# ButtonsBuzzerLeds.net
KiCad netlist of a schematic drawn in Altium Designer
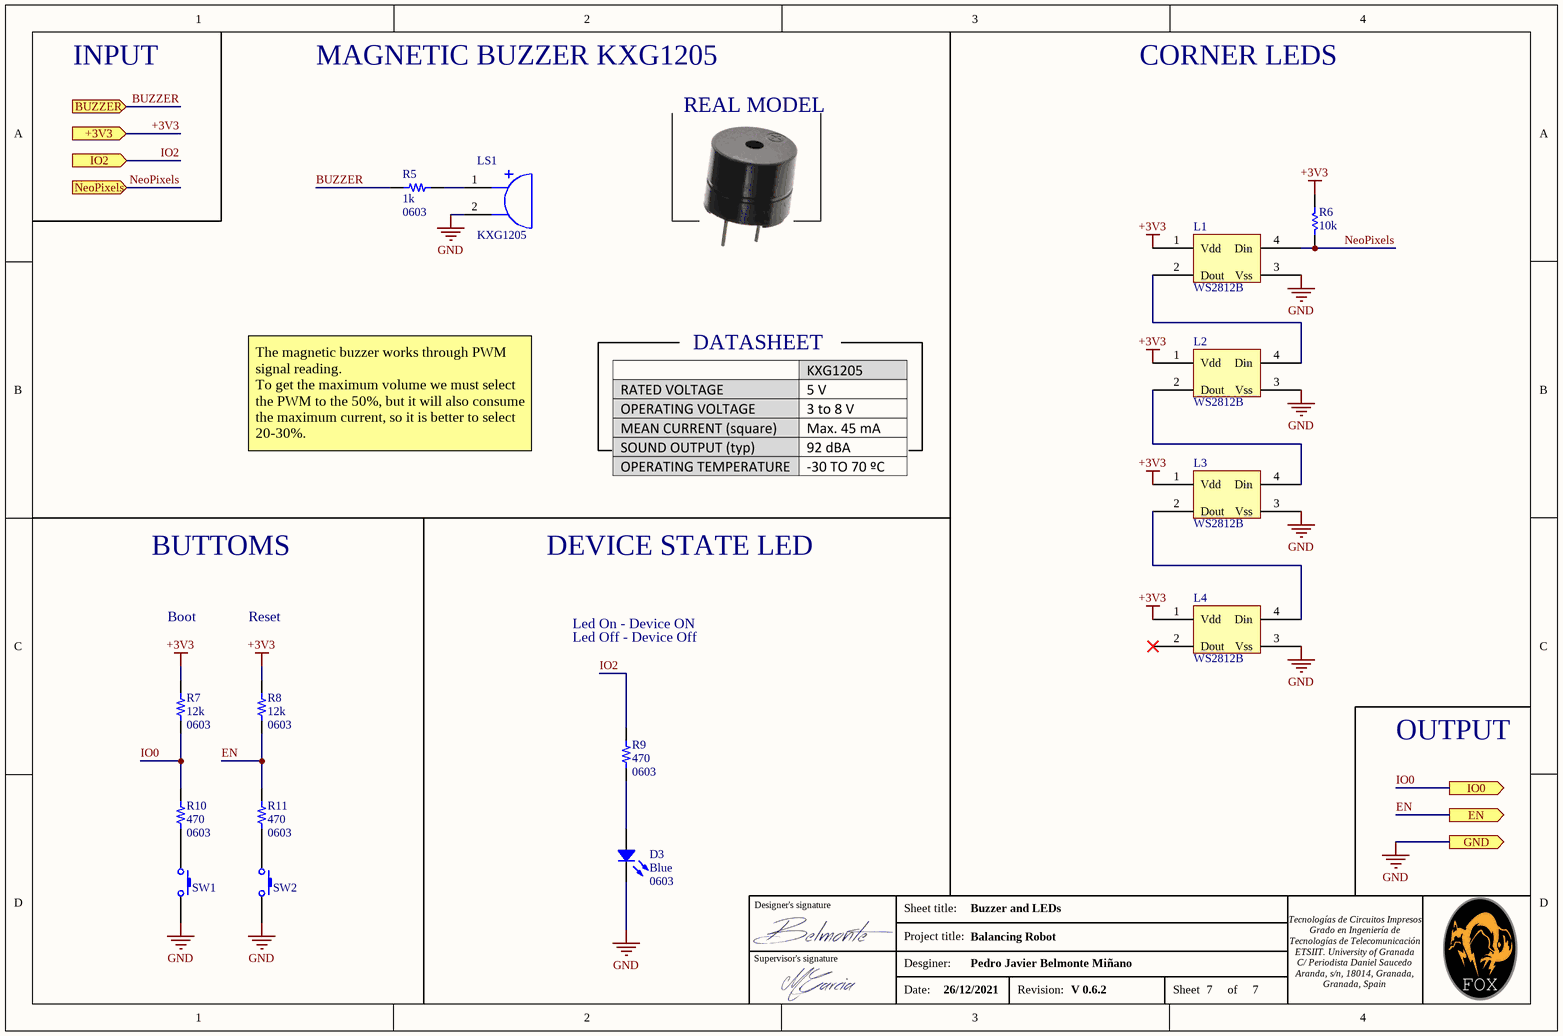
[diagram p0: ButtonsBuzzerLeds.SchDoc]

(export (version "E")
  (design (tool "Eeschema 10.0.6"))
  (components
    (comp (ref "D3")
      (value "Blue")
      (footprint "LED 0603_1608 BLUE")
      (description "LED BLUE 0603 SMD")
      (fields
        (field (name "PART NUMBER") "VLMB1300-GS08")
        (field (name "MANUFACTURER") "Vishay Semiconductor Opto Division")
        (field (name "SIZE") "0603")
      )
      (libsource (lib "ControlBoard") (part "LED"))
    )
    (comp (ref "L1")
      (value "WS2812B")
      (footprint "WS2812B")
      (libsource (lib "HeimdalLimiter") (part "WS2812B"))
    )
    (comp (ref "L2")
      (value "WS2812B")
      (footprint "WS2812B")
      (libsource (lib "HeimdalLimiter") (part "WS2812B"))
    )
    (comp (ref "L3")
      (value "WS2812B")
      (footprint "WS2812B")
      (libsource (lib "HeimdalLimiter") (part "WS2812B"))
    )
    (comp (ref "L4")
      (value "WS2812B")
      (footprint "WS2812B")
      (libsource (lib "HeimdalLimiter") (part "WS2812B"))
    )
    (comp (ref "LS1") (value "KXG1205") (footprint "BUZZER") (libsource (lib "ControlBoard") (part "Buzzer")))
    (comp (ref "R5")
      (value "1k")
      (footprint "RES 0603_1608")
      (description "RES SMD 1K OHM 1% 1/4W 0603")
      (fields
        (field (name "PART NUMBER") "CRCW06031K00FKEAHP")
        (field (name "MANUFACTURER") "Vishay Dale")
        (field (name "SIZE") "0603")
      )
      (libsource (lib "ControlBoard") (part "CRCW06031K00FKEAHP"))
    )
    (comp (ref "R6")
      (value "10k")
      (footprint "0805")
      (description "Resistor")
      (libsource (lib "HeimdalLimiter") (part "Resistor"))
    )
    (comp (ref "R7")
      (value "12k")
      (footprint "RES 0603_1608")
      (description "RES 12K OHM 5% 1/10W 0603")
      (fields
        (field (name "PART NUMBER") "RMCF0603JT12K0")
        (field (name "MANUFACTURER") "Stackpole Electronics Inc")
        (field (name "SIZE") "0603")
      )
      (libsource (lib "ControlBoard") (part "RMCF0603JT12K0"))
    )
    (comp (ref "R8")
      (value "12k")
      (footprint "RES 0603_1608")
      (description "RES 12K OHM 5% 1/10W 0603")
      (fields
        (field (name "PART NUMBER") "RMCF0603JT12K0")
        (field (name "MANUFACTURER") "Stackpole Electronics Inc")
        (field (name "SIZE") "0603")
      )
      (libsource (lib "ControlBoard") (part "RMCF0603JT12K0"))
    )
    (comp (ref "R9")
      (value "470")
      (footprint "RES 0603_1608")
      (description "RES 470 OHM 5% 1/10W 0603")
      (fields
        (field (name "PART NUMBER") "RMCF0603JT470R")
        (field (name "MANUFACTURER") "Stackpole Electronics Inc")
        (field (name "SIZE") "0603")
      )
      (libsource (lib "ControlBoard") (part "RMCF0603JT470R"))
    )
    (comp (ref "R10")
      (value "470")
      (footprint "RES 0603_1608")
      (description "RES 470 OHM 5% 1/10W 0603")
      (fields
        (field (name "PART NUMBER") "RMCF0603JT470R")
        (field (name "MANUFACTURER") "Stackpole Electronics Inc")
        (field (name "SIZE") "0603")
      )
      (libsource (lib "ControlBoard") (part "RMCF0603JT470R"))
    )
    (comp (ref "R11")
      (value "470")
      (footprint "RES 0603_1608")
      (description "RES 470 OHM 5% 1/10W 0603")
      (fields
        (field (name "PART NUMBER") "RMCF0603JT470R")
        (field (name "MANUFACTURER") "Stackpole Electronics Inc")
        (field (name "SIZE") "0603")
      )
      (libsource (lib "ControlBoard") (part "RMCF0603JT470R"))
    )
    (comp (ref "SW1")
      (value "FSMSMTR")
      (footprint "TECO-FSMSMTR_V")
      (description "FSMSM Push Button Switch, 50 mA, -35 to 85 degC, 2-Pin SMD, RoHS, Tape and Reel")
      (fields (field (name "MANUFACTURER") "TE Connectivity"))
      (libsource (lib "TopBoardLib") (part "CMP-2000-07501-1"))
    )
    (comp (ref "SW2")
      (value "FSMSMTR")
      (footprint "TECO-FSMSMTR_V")
      (description "FSMSM Push Button Switch, 50 mA, -35 to 85 degC, 2-Pin SMD, RoHS, Tape and Reel")
      (fields (field (name "MANUFACTURER") "TE Connectivity"))
      (libsource (lib "TopBoardLib") (part "CMP-2000-07501-1"))
    )
  )
  (nets
    (net (code "1") (name "+3V3") (class "Default")
      (node (ref "L1") (pin "1") (pinfunction "Vdd_1") (pintype "passive"))
      (node (ref "L2") (pin "1") (pinfunction "Vdd_1") (pintype "passive"))
      (node (ref "L3") (pin "1") (pinfunction "Vdd_1") (pintype "passive"))
      (node (ref "L4") (pin "1") (pinfunction "Vdd_1") (pintype "passive"))
      (node (ref "R6") (pin "1") (pinfunction "1_1") (pintype "passive"))
      (node (ref "R7") (pin "1") (pinfunction "1_1") (pintype "passive"))
      (node (ref "R8") (pin "1") (pinfunction "1_1") (pintype "passive"))
    )
    (net (code "2") (name "/BUZZER") (class "Default")
      (node (ref "R5") (pin "2") (pinfunction "2_2") (pintype "passive"))
    )
    (net (code "3") (name "/EN") (class "Default")
      (node (ref "R11") (pin "1") (pinfunction "1_1") (pintype "passive"))
      (node (ref "R8") (pin "2") (pinfunction "2_2") (pintype "passive"))
    )
    (net (code "4") (name "/IO0") (class "Default")
      (node (ref "R10") (pin "1") (pinfunction "1_1") (pintype "passive"))
      (node (ref "R7") (pin "2") (pinfunction "2_2") (pintype "passive"))
    )
    (net (code "5") (name "/IO2") (class "Default")
      (node (ref "R9") (pin "1") (pinfunction "1_1") (pintype "passive"))
    )
    (net (code "6") (name "/NeoPixels") (class "Default")
      (node (ref "L1") (pin "4") (pinfunction "Din_4") (pintype "passive"))
      (node (ref "R6") (pin "2") (pinfunction "2_2") (pintype "passive"))
    )
    (net (code "7") (name "GND") (class "Default")
      (node (ref "D3") (pin "2") (pinfunction "2_2") (pintype "passive"))
      (node (ref "L1") (pin "3") (pinfunction "Vss_3") (pintype "passive"))
      (node (ref "L2") (pin "3") (pinfunction "Vss_3") (pintype "passive"))
      (node (ref "L3") (pin "3") (pinfunction "Vss_3") (pintype "passive"))
      (node (ref "L4") (pin "3") (pinfunction "Vss_3") (pintype "passive"))
      (node (ref "LS1") (pin "2") (pinfunction "-_2") (pintype "passive"))
      (node (ref "SW1") (pin "2") (pinfunction "2_2") (pintype "passive"))
      (node (ref "SW2") (pin "2") (pinfunction "2_2") (pintype "passive"))
    )
    (net (code "8") (name "Net-(D3-Pad1)") (class "Default")
      (node (ref "D3") (pin "1") (pinfunction "1_1") (pintype "passive"))
      (node (ref "R9") (pin "2") (pinfunction "2_2") (pintype "passive"))
    )
    (net (code "9") (name "Net-(L1-Dout)") (class "Default")
      (node (ref "L1") (pin "2") (pinfunction "Dout_2") (pintype "passive"))
      (node (ref "L2") (pin "4") (pinfunction "Din_4") (pintype "passive"))
    )
    (net (code "10") (name "Net-(L2-Dout)") (class "Default")
      (node (ref "L2") (pin "2") (pinfunction "Dout_2") (pintype "passive"))
      (node (ref "L3") (pin "4") (pinfunction "Din_4") (pintype "passive"))
    )
    (net (code "11") (name "Net-(L3-Dout)") (class "Default")
      (node (ref "L3") (pin "2") (pinfunction "Dout_2") (pintype "passive"))
      (node (ref "L4") (pin "4") (pinfunction "Din_4") (pintype "passive"))
    )
    (net (code "12") (name "Net-(LS1-+)") (class "Default")
      (node (ref "LS1") (pin "1") (pinfunction "+_1") (pintype "passive"))
      (node (ref "R5") (pin "1") (pinfunction "1_1") (pintype "passive"))
    )
    (net (code "13") (name "Net-(R10-Pad2)") (class "Default")
      (node (ref "R10") (pin "2") (pinfunction "2_2") (pintype "passive"))
      (node (ref "SW1") (pin "1") (pinfunction "1_1") (pintype "passive"))
    )
    (net (code "14") (name "Net-(R11-Pad2)") (class "Default")
      (node (ref "R11") (pin "2") (pinfunction "2_2") (pintype "passive"))
      (node (ref "SW2") (pin "1") (pinfunction "1_1") (pintype "passive"))
    )
    (net (code "15") (name "unconnected-(L4-Dout-Pad2)") (class "Default")
      (node (ref "L4") (pin "2") (pinfunction "Dout_2") (pintype "passive+no_connect"))
    )
  )
)
